# memoryboard4.net
KiCad netlist of a schematic drawn in EAGLE
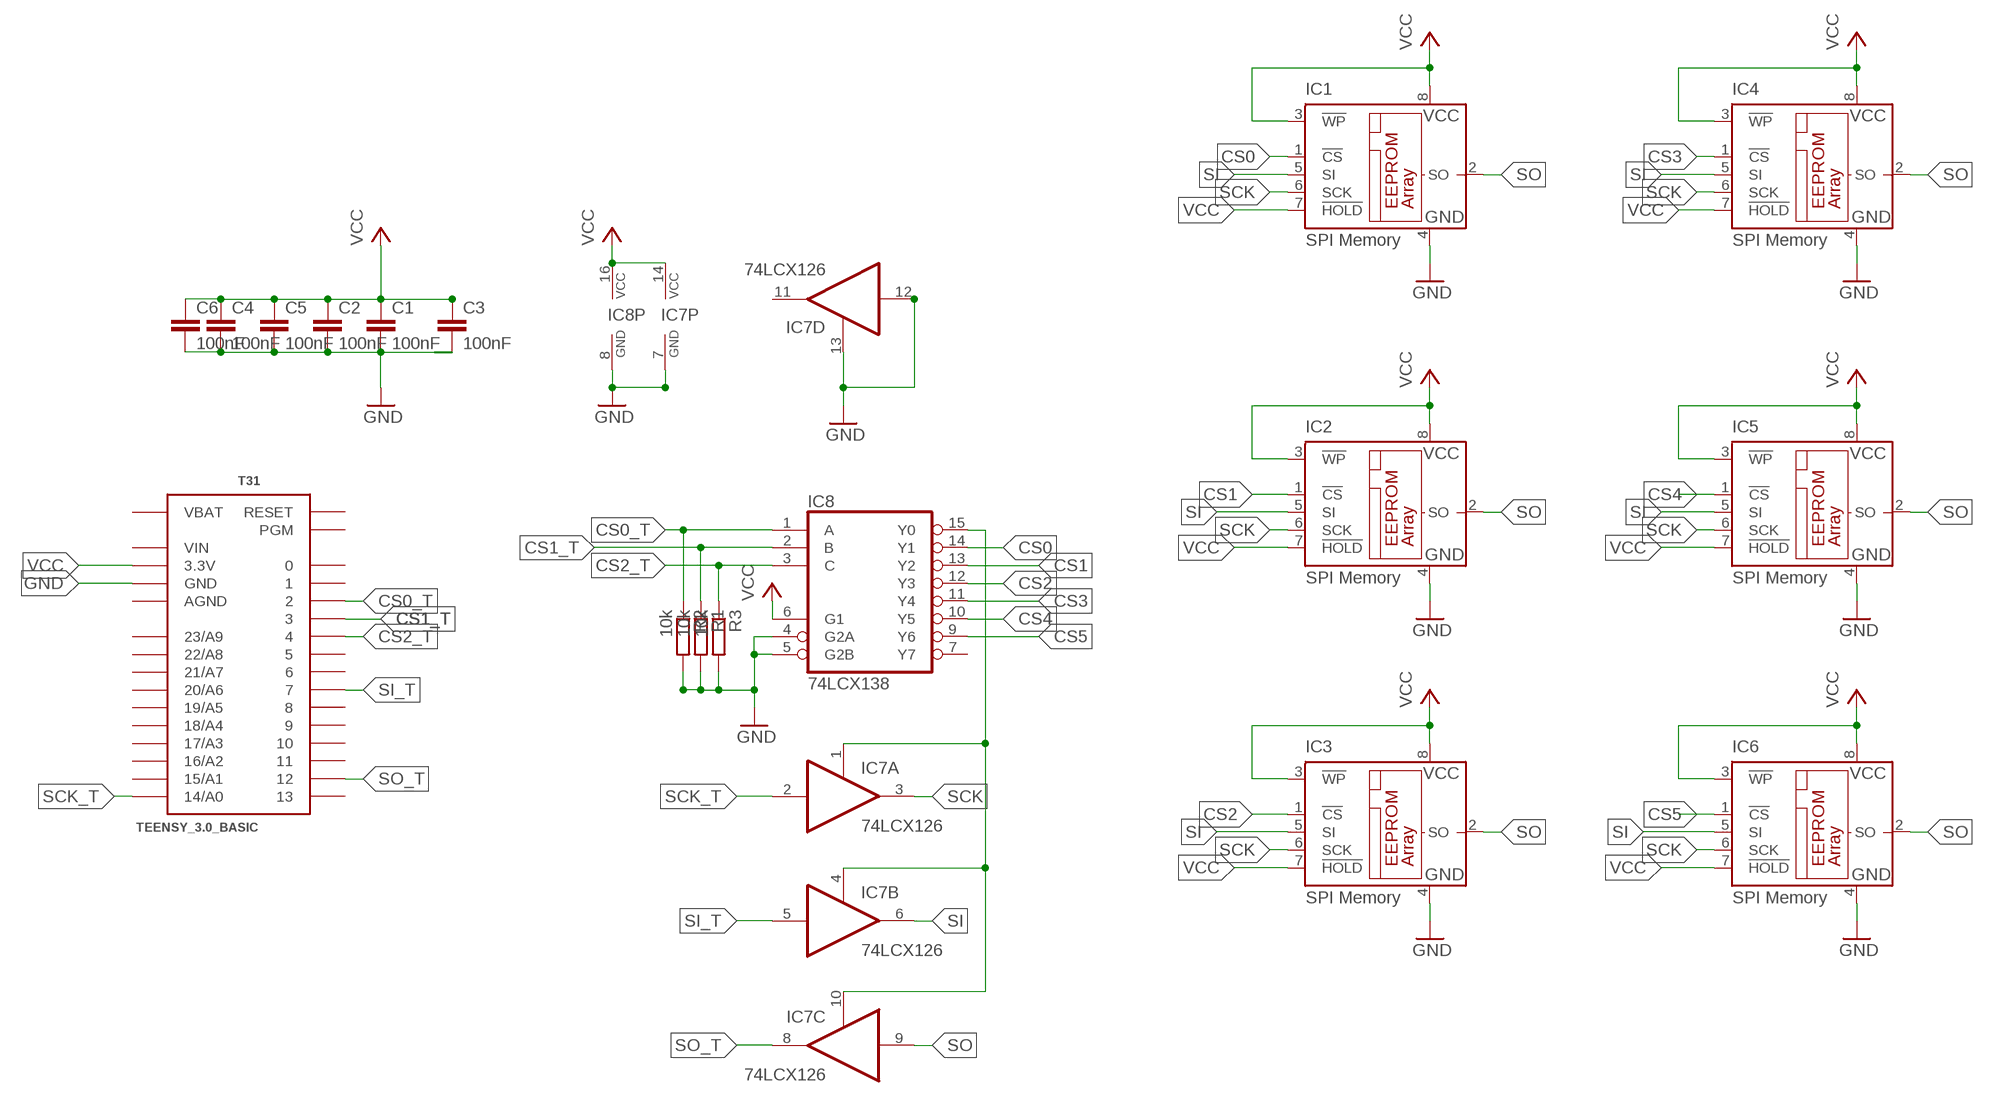
[diagram p0: schematic, sheet 1]

(export (version "E")
  (design (tool "Eeschema 10.0.6"))
  (components
    (comp (ref "C1")
      (value "100nF")
      (footprint "eagle-import:C0603")
      (libsource (lib "eagle-import") (part "C-EUC0603"))
    )
    (comp (ref "C2")
      (value "100nF")
      (footprint "eagle-import:C0603")
      (libsource (lib "eagle-import") (part "C-EUC0603"))
    )
    (comp (ref "C3")
      (value "100nF")
      (footprint "eagle-import:C0603")
      (libsource (lib "eagle-import") (part "C-EUC0603"))
    )
    (comp (ref "C4")
      (value "100nF")
      (footprint "eagle-import:C0603")
      (libsource (lib "eagle-import") (part "C-EUC0603"))
    )
    (comp (ref "C5")
      (value "100nF")
      (footprint "eagle-import:C0603")
      (libsource (lib "eagle-import") (part "C-EUC0603"))
    )
    (comp (ref "C6")
      (value "100nF")
      (footprint "eagle-import:C0603")
      (libsource (lib "eagle-import") (part "C-EUC0603"))
    )
    (comp (ref "IC1")
      (value "SPI Memory")
      (footprint "eagle-import:SO-08")
      (fields (field (name "MF") "MICROCHIP") (field (name "MPN") "25C080/SN"))
      (libsource (lib "eagle-import") (part "25SNC080"))
    )
    (comp (ref "IC2")
      (value "SPI Memory")
      (footprint "eagle-import:SO-08")
      (fields (field (name "MF") "MICROCHIP") (field (name "MPN") "25C080/SN"))
      (libsource (lib "eagle-import") (part "25SNC080"))
    )
    (comp (ref "IC3")
      (value "SPI Memory")
      (footprint "eagle-import:SO-08")
      (fields (field (name "MF") "MICROCHIP") (field (name "MPN") "25C080/SN"))
      (libsource (lib "eagle-import") (part "25SNC080"))
    )
    (comp (ref "IC4")
      (value "SPI Memory")
      (footprint "eagle-import:SO-08")
      (fields (field (name "MF") "MICROCHIP") (field (name "MPN") "25C080/SN"))
      (libsource (lib "eagle-import") (part "25SNC080"))
    )
    (comp (ref "IC5")
      (value "SPI Memory")
      (footprint "eagle-import:SO-08")
      (fields (field (name "MF") "MICROCHIP") (field (name "MPN") "25C080/SN"))
      (libsource (lib "eagle-import") (part "25SNC080"))
    )
    (comp (ref "IC6")
      (value "SPI Memory")
      (footprint "eagle-import:SO-08")
      (fields (field (name "MF") "MICROCHIP") (field (name "MPN") "25C080/SN"))
      (libsource (lib "eagle-import") (part "25SNC080"))
    )
    (comp (ref "IC7")
      (value "74LCX126")
      (footprint "eagle-import:SO14")
      (libsource (lib "eagle-import") (part "74126DAC"))
    )
    (comp (ref "IC8")
      (value "74LCX138")
      (footprint "eagle-import:SO16")
      (libsource (lib "eagle-import") (part "74138DHC"))
    )
    (comp (ref "R1")
      (value "10k")
      (footprint "eagle-import:R0603")
      (libsource (lib "eagle-import") (part "R-EU_R0603"))
    )
    (comp (ref "R2")
      (value "10k")
      (footprint "eagle-import:R0603")
      (libsource (lib "eagle-import") (part "R-EU_R0603"))
    )
    (comp (ref "R3")
      (value "10k")
      (footprint "eagle-import:R0603")
      (libsource (lib "eagle-import") (part "R-EU_R0603"))
    )
    (comp (ref "T31")
      (value "TEENSY_3.0_BASIC")
      (footprint "eagle-import:TEENSY_3.0_BASIC")
      (libsource (lib "eagle-import") (part "TEENSY_3.0_BASIC"))
    )
  )
  (nets
    (net (code "1") (name "/AGND") (class "Default")
      (node (ref "T31") (pin "AGND") (pinfunction "AGND_AGND") (pintype "power_in"))
    )
    (net (code "2") (name "/VBAT") (class "Default")
      (node (ref "T31") (pin "VBAT") (pinfunction "VBAT_VBAT") (pintype "power_in"))
    )
    (net (code "3") (name "/VIN") (class "Default")
      (node (ref "T31") (pin "VIN") (pinfunction "VIN_VIN") (pintype "power_in"))
    )
    (net (code "4") (name "CS0") (class "Default")
      (node (ref "IC1") (pin "1") (pinfunction "~{CS}_1") (pintype "input"))
      (node (ref "IC8") (pin "14") (pinfunction "Y1_14") (pintype "output"))
    )
    (net (code "5") (name "CS0_T") (class "Default")
      (node (ref "IC8") (pin "1") (pinfunction "A_1") (pintype "input"))
      (node (ref "R2") (pin "1") (pinfunction "1_1") (pintype "passive"))
      (node (ref "T31") (pin "2") (pinfunction "2_2") (pintype "bidirectional"))
    )
    (net (code "6") (name "CS1") (class "Default")
      (node (ref "IC2") (pin "1") (pinfunction "~{CS}_1") (pintype "input"))
      (node (ref "IC8") (pin "13") (pinfunction "Y2_13") (pintype "output"))
    )
    (net (code "7") (name "CS1_T") (class "Default")
      (node (ref "IC8") (pin "2") (pinfunction "B_2") (pintype "input"))
      (node (ref "R1") (pin "1") (pinfunction "1_1") (pintype "passive"))
      (node (ref "T31") (pin "3") (pinfunction "3_3") (pintype "bidirectional"))
    )
    (net (code "8") (name "CS2") (class "Default")
      (node (ref "IC3") (pin "1") (pinfunction "~{CS}_1") (pintype "input"))
      (node (ref "IC8") (pin "12") (pinfunction "Y3_12") (pintype "output"))
    )
    (net (code "9") (name "CS2_T") (class "Default")
      (node (ref "IC8") (pin "3") (pinfunction "C_3") (pintype "input"))
      (node (ref "R3") (pin "1") (pinfunction "1_1") (pintype "passive"))
      (node (ref "T31") (pin "4") (pinfunction "4_4") (pintype "bidirectional"))
    )
    (net (code "10") (name "CS3") (class "Default")
      (node (ref "IC4") (pin "1") (pinfunction "~{CS}_1") (pintype "input"))
      (node (ref "IC8") (pin "11") (pinfunction "Y4_11") (pintype "output"))
    )
    (net (code "11") (name "CS4") (class "Default")
      (node (ref "IC5") (pin "1") (pinfunction "~{CS}_1") (pintype "input"))
      (node (ref "IC8") (pin "10") (pinfunction "Y5_10") (pintype "output"))
    )
    (net (code "12") (name "CS5") (class "Default")
      (node (ref "IC6") (pin "1") (pinfunction "~{CS}_1") (pintype "input"))
      (node (ref "IC8") (pin "9") (pinfunction "Y6_9") (pintype "output"))
    )
    (net (code "13") (name "GND") (class "Default")
      (node (ref "C1") (pin "2") (pinfunction "2_2") (pintype "passive"))
      (node (ref "C2") (pin "2") (pinfunction "2_2") (pintype "passive"))
      (node (ref "C3") (pin "2") (pinfunction "2_2") (pintype "passive"))
      (node (ref "C4") (pin "2") (pinfunction "2_2") (pintype "passive"))
      (node (ref "C5") (pin "2") (pinfunction "2_2") (pintype "passive"))
      (node (ref "C6") (pin "2") (pinfunction "2_2") (pintype "passive"))
      (node (ref "IC1") (pin "4") (pinfunction "GND_4") (pintype "power_in"))
      (node (ref "IC2") (pin "4") (pinfunction "GND_4") (pintype "power_in"))
      (node (ref "IC3") (pin "4") (pinfunction "GND_4") (pintype "power_in"))
      (node (ref "IC4") (pin "4") (pinfunction "GND_4") (pintype "power_in"))
      (node (ref "IC5") (pin "4") (pinfunction "GND_4") (pintype "power_in"))
      (node (ref "IC6") (pin "4") (pinfunction "GND_4") (pintype "power_in"))
      (node (ref "IC7") (pin "12") (pinfunction "I_12") (pintype "input"))
      (node (ref "IC7") (pin "13") (pinfunction "OE_13") (pintype "input"))
      (node (ref "IC7") (pin "7") (pinfunction "GND_7") (pintype "power_in"))
      (node (ref "IC8") (pin "4") (pinfunction "G2A_4") (pintype "input"))
      (node (ref "IC8") (pin "5") (pinfunction "G2B_5") (pintype "input"))
      (node (ref "IC8") (pin "8") (pinfunction "GND_8") (pintype "power_in"))
      (node (ref "R1") (pin "2") (pinfunction "2_2") (pintype "passive"))
      (node (ref "R2") (pin "2") (pinfunction "2_2") (pintype "passive"))
      (node (ref "R3") (pin "2") (pinfunction "2_2") (pintype "passive"))
      (node (ref "T31") (pin "GND") (pinfunction "GND_GND") (pintype "power_in"))
      (node (ref "T31") (pin "GND1") (pinfunction "GND_GND1") (pintype "power_in"))
    )
    (net (code "14") (name "Net-(IC7A-OE)") (class "Default")
      (node (ref "IC7") (pin "1") (pinfunction "OE_1") (pintype "input"))
      (node (ref "IC7") (pin "10") (pinfunction "OE_10") (pintype "input"))
      (node (ref "IC7") (pin "4") (pinfunction "OE_4") (pintype "input"))
      (node (ref "IC8") (pin "15") (pinfunction "Y0_15") (pintype "output"))
    )
    (net (code "15") (name "SCK") (class "Default")
      (node (ref "IC1") (pin "6") (pinfunction "SCK_6") (pintype "input"))
      (node (ref "IC2") (pin "6") (pinfunction "SCK_6") (pintype "input"))
      (node (ref "IC3") (pin "6") (pinfunction "SCK_6") (pintype "input"))
      (node (ref "IC4") (pin "6") (pinfunction "SCK_6") (pintype "input"))
      (node (ref "IC5") (pin "6") (pinfunction "SCK_6") (pintype "input"))
      (node (ref "IC6") (pin "6") (pinfunction "SCK_6") (pintype "input"))
      (node (ref "IC7") (pin "3") (pinfunction "O_3") (pintype "output"))
    )
    (net (code "16") (name "SCK_T") (class "Default")
      (node (ref "IC7") (pin "2") (pinfunction "I_2") (pintype "input"))
      (node (ref "T31") (pin "14/A0") (pinfunction "14/A0_14/A0") (pintype "bidirectional"))
    )
    (net (code "17") (name "SI") (class "Default")
      (node (ref "IC1") (pin "5") (pinfunction "SI_5") (pintype "input"))
      (node (ref "IC2") (pin "5") (pinfunction "SI_5") (pintype "input"))
      (node (ref "IC3") (pin "5") (pinfunction "SI_5") (pintype "input"))
      (node (ref "IC4") (pin "5") (pinfunction "SI_5") (pintype "input"))
      (node (ref "IC5") (pin "5") (pinfunction "SI_5") (pintype "input"))
      (node (ref "IC6") (pin "5") (pinfunction "SI_5") (pintype "input"))
      (node (ref "IC7") (pin "6") (pinfunction "O_6") (pintype "output"))
    )
    (net (code "18") (name "SI_T") (class "Default")
      (node (ref "IC7") (pin "5") (pinfunction "I_5") (pintype "input"))
      (node (ref "T31") (pin "7") (pinfunction "7_7") (pintype "bidirectional"))
    )
    (net (code "19") (name "SO") (class "Default")
      (node (ref "IC1") (pin "2") (pinfunction "SO_2") (pintype "bidirectional"))
      (node (ref "IC2") (pin "2") (pinfunction "SO_2") (pintype "bidirectional"))
      (node (ref "IC3") (pin "2") (pinfunction "SO_2") (pintype "bidirectional"))
      (node (ref "IC4") (pin "2") (pinfunction "SO_2") (pintype "bidirectional"))
      (node (ref "IC5") (pin "2") (pinfunction "SO_2") (pintype "bidirectional"))
      (node (ref "IC6") (pin "2") (pinfunction "SO_2") (pintype "bidirectional"))
      (node (ref "IC7") (pin "9") (pinfunction "I_9") (pintype "input"))
    )
    (net (code "20") (name "SO_T") (class "Default")
      (node (ref "IC7") (pin "8") (pinfunction "O_8") (pintype "output"))
      (node (ref "T31") (pin "12") (pinfunction "12_12") (pintype "bidirectional"))
    )
    (net (code "21") (name "VCC") (class "Default")
      (node (ref "C1") (pin "1") (pinfunction "1_1") (pintype "passive"))
      (node (ref "C2") (pin "1") (pinfunction "1_1") (pintype "passive"))
      (node (ref "C3") (pin "1") (pinfunction "1_1") (pintype "passive"))
      (node (ref "C4") (pin "1") (pinfunction "1_1") (pintype "passive"))
      (node (ref "C5") (pin "1") (pinfunction "1_1") (pintype "passive"))
      (node (ref "C6") (pin "1") (pinfunction "1_1") (pintype "passive"))
      (node (ref "IC1") (pin "3") (pinfunction "~{WP}_3") (pintype "input"))
      (node (ref "IC1") (pin "7") (pinfunction "~{HOLD}_7") (pintype "input"))
      (node (ref "IC1") (pin "8") (pinfunction "VCC_8") (pintype "power_in"))
      (node (ref "IC2") (pin "3") (pinfunction "~{WP}_3") (pintype "input"))
      (node (ref "IC2") (pin "7") (pinfunction "~{HOLD}_7") (pintype "input"))
      (node (ref "IC2") (pin "8") (pinfunction "VCC_8") (pintype "power_in"))
      (node (ref "IC3") (pin "3") (pinfunction "~{WP}_3") (pintype "input"))
      (node (ref "IC3") (pin "7") (pinfunction "~{HOLD}_7") (pintype "input"))
      (node (ref "IC3") (pin "8") (pinfunction "VCC_8") (pintype "power_in"))
      (node (ref "IC4") (pin "3") (pinfunction "~{WP}_3") (pintype "input"))
      (node (ref "IC4") (pin "7") (pinfunction "~{HOLD}_7") (pintype "input"))
      (node (ref "IC4") (pin "8") (pinfunction "VCC_8") (pintype "power_in"))
      (node (ref "IC5") (pin "3") (pinfunction "~{WP}_3") (pintype "input"))
      (node (ref "IC5") (pin "7") (pinfunction "~{HOLD}_7") (pintype "input"))
      (node (ref "IC5") (pin "8") (pinfunction "VCC_8") (pintype "power_in"))
      (node (ref "IC6") (pin "3") (pinfunction "~{WP}_3") (pintype "input"))
      (node (ref "IC6") (pin "7") (pinfunction "~{HOLD}_7") (pintype "input"))
      (node (ref "IC6") (pin "8") (pinfunction "VCC_8") (pintype "power_in"))
      (node (ref "IC7") (pin "14") (pinfunction "VCC_14") (pintype "power_in"))
      (node (ref "IC8") (pin "16") (pinfunction "VCC_16") (pintype "power_in"))
      (node (ref "IC8") (pin "6") (pinfunction "G1_6") (pintype "input"))
      (node (ref "T31") (pin "3.3V") (pinfunction "3.3V_3.3V") (pintype "power_in"))
      (node (ref "T31") (pin "3.3V1") (pinfunction "3.3V_3.3V1") (pintype "power_in"))
    )
    (net (code "22") (name "unconnected-(IC7D-O-Pad11)") (class "Default")
      (node (ref "IC7") (pin "11") (pinfunction "O_11") (pintype "output"))
    )
    (net (code "23") (name "unconnected-(IC8A-Y7-Pad7)") (class "Default")
      (node (ref "IC8") (pin "7") (pinfunction "Y7_7") (pintype "output"))
    )
    (net (code "24") (name "unconnected-(T31-Pad0)") (class "Default")
      (node (ref "T31") (pin "0") (pinfunction "0_0") (pintype "bidirectional"))
    )
    (net (code "25") (name "unconnected-(T31-Pad1)") (class "Default")
      (node (ref "T31") (pin "1") (pinfunction "1_1") (pintype "bidirectional"))
    )
    (net (code "26") (name "unconnected-(T31-Pad5)") (class "Default")
      (node (ref "T31") (pin "5") (pinfunction "5_5") (pintype "bidirectional"))
    )
    (net (code "27") (name "unconnected-(T31-Pad6)") (class "Default")
      (node (ref "T31") (pin "6") (pinfunction "6_6") (pintype "bidirectional"))
    )
    (net (code "28") (name "unconnected-(T31-Pad8)") (class "Default")
      (node (ref "T31") (pin "8") (pinfunction "8_8") (pintype "bidirectional"))
    )
    (net (code "29") (name "unconnected-(T31-Pad9)") (class "Default")
      (node (ref "T31") (pin "9") (pinfunction "9_9") (pintype "bidirectional"))
    )
    (net (code "30") (name "unconnected-(T31-Pad10)") (class "Default")
      (node (ref "T31") (pin "10") (pinfunction "10_10") (pintype "bidirectional"))
    )
    (net (code "31") (name "unconnected-(T31-Pad11)") (class "Default")
      (node (ref "T31") (pin "11") (pinfunction "11_11") (pintype "bidirectional"))
    )
    (net (code "32") (name "unconnected-(T31-Pad13)") (class "Default")
      (node (ref "T31") (pin "13") (pinfunction "13_13") (pintype "bidirectional"))
    )
    (net (code "33") (name "unconnected-(T31-Pad15{slash}A1)") (class "Default")
      (node (ref "T31") (pin "15/A1") (pinfunction "15/A1_15/A1") (pintype "bidirectional"))
    )
    (net (code "34") (name "unconnected-(T31-Pad16{slash}A2)") (class "Default")
      (node (ref "T31") (pin "16/A2") (pinfunction "16/A2_16/A2") (pintype "bidirectional"))
    )
    (net (code "35") (name "unconnected-(T31-Pad17{slash}A3)") (class "Default")
      (node (ref "T31") (pin "17/A3") (pinfunction "17/A3_17/A3") (pintype "bidirectional"))
    )
    (net (code "36") (name "unconnected-(T31-Pad18{slash}A4)") (class "Default")
      (node (ref "T31") (pin "18/A4") (pinfunction "18/A4_18/A4") (pintype "bidirectional"))
    )
    (net (code "37") (name "unconnected-(T31-Pad19{slash}A5)") (class "Default")
      (node (ref "T31") (pin "19/A5") (pinfunction "19/A5_19/A5") (pintype "bidirectional"))
    )
    (net (code "38") (name "unconnected-(T31-Pad20{slash}A6)") (class "Default")
      (node (ref "T31") (pin "20/A6") (pinfunction "20/A6_20/A6") (pintype "bidirectional"))
    )
    (net (code "39") (name "unconnected-(T31-Pad21{slash}A7)") (class "Default")
      (node (ref "T31") (pin "21/A7") (pinfunction "21/A7_21/A7") (pintype "bidirectional"))
    )
    (net (code "40") (name "unconnected-(T31-Pad22{slash}A8)") (class "Default")
      (node (ref "T31") (pin "22/A8") (pinfunction "22/A8_22/A8") (pintype "bidirectional"))
    )
    (net (code "41") (name "unconnected-(T31-Pad23{slash}A9)") (class "Default")
      (node (ref "T31") (pin "23/A9") (pinfunction "23/A9_23/A9") (pintype "bidirectional"))
    )
    (net (code "42") (name "unconnected-(T31-PadPGM)") (class "Default")
      (node (ref "T31") (pin "PGM") (pinfunction "PGM_PGM") (pintype "bidirectional"))
    )
    (net (code "43") (name "unconnected-(T31-PadRESET)") (class "Default")
      (node (ref "T31") (pin "RESET") (pinfunction "RESET_RESET") (pintype "bidirectional"))
    )
  )
)
